# 03_mcu_oscillators.net
KiCad netlist of a schematic drawn in Altium Designer
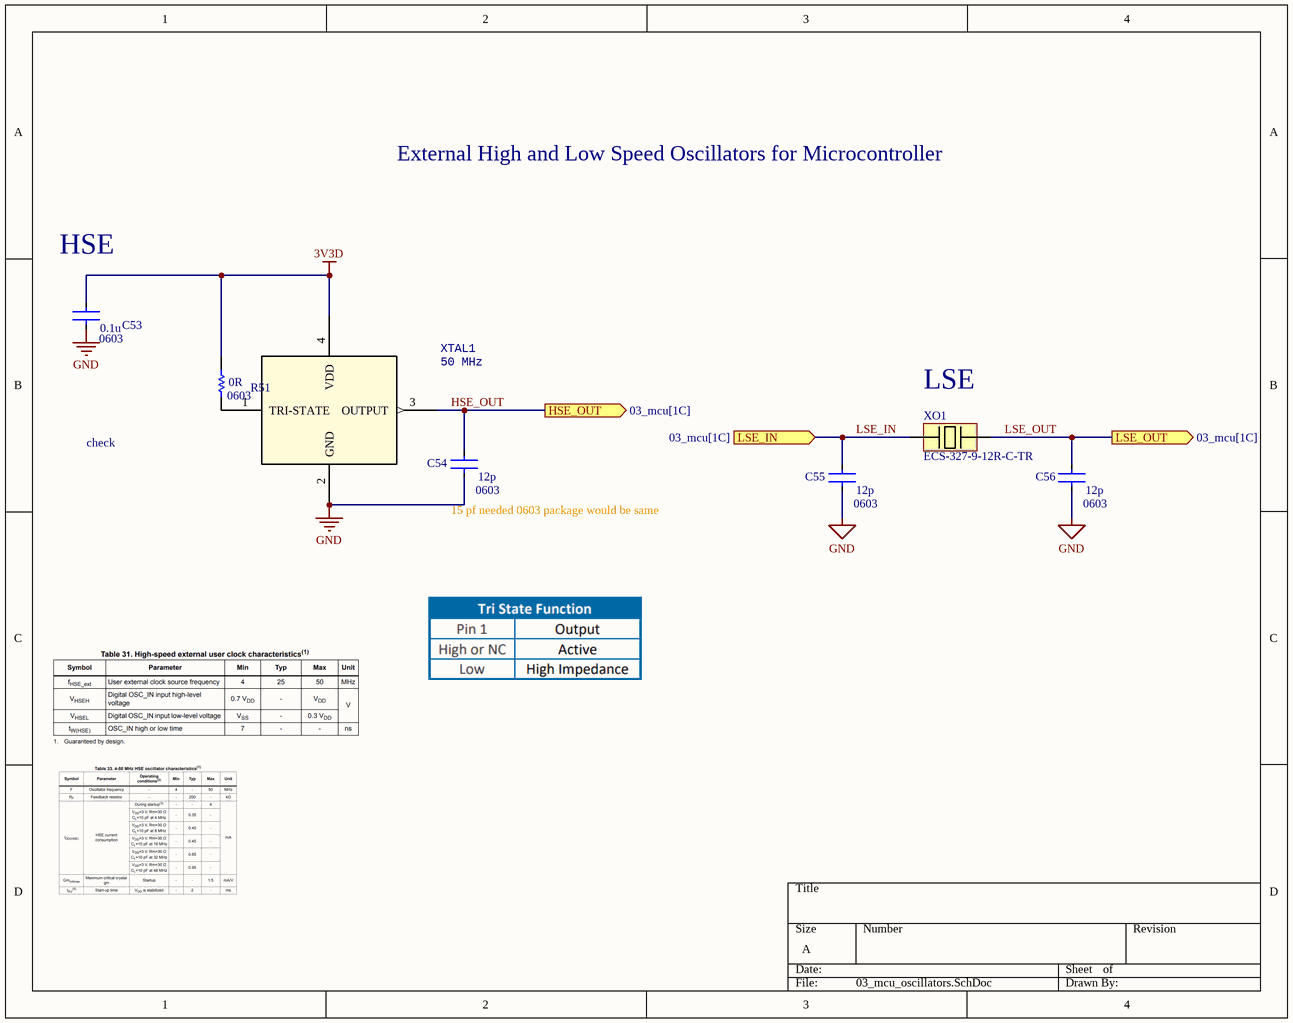
[diagram p0: 03_mcu_oscillators.SchDoc]

(export (version "E")
  (design (tool "Eeschema 10.0.6"))
  (components
    (comp (ref "C53")
      (value "CGA3E2X7R1H104K080AA")
      (footprint "CAPTDK0603")
      (description "CAP CER 0.1UF 50V X7R 0603")
      (libsource (lib "tcspc00") (part "CGA3E2X7R1H104K080AA"))
    )
    (comp (ref "C54")
      (value "CGA3E2C0G1H120J080AA")
      (footprint "CAPTDK0603")
      (description "CAP CER 12PF 50V C0G 0603")
      (libsource (lib "tcspc00") (part "CGA3E2C0G1H120J080AA"))
    )
    (comp (ref "C55")
      (value "CGA3E2C0G1H120J080AA")
      (footprint "CAPTDK0603")
      (description "CAP CER 12PF 50V C0G 0603")
      (libsource (lib "tcspc00") (part "CGA3E2C0G1H120J080AA"))
    )
    (comp (ref "C56")
      (value "CGA3E2C0G1H120J080AA")
      (footprint "CAPTDK0603")
      (description "CAP CER 12PF 50V C0G 0603")
      (libsource (lib "tcspc00") (part "CGA3E2C0G1H120J080AA"))
    )
    (comp (ref "R51")
      (value "RMCF0603ZT0R00")
      (footprint "RES-STACK-POLE-0603")
      (description "RES 0 OHM JUMPER 1/10W 0603")
      (libsource (lib "tcspc00") (part "RMCF0603ZT0R00"))
    )
    (comp (ref "XO1")
      (value "ECS-327-9-12R-C-TR")
      (footprint "LSE-32K")
      (description "Crystal 0.032768MHz ±10ppm (Tol) 9pF Flexural 70000Ohm Automotive 2-Pin Ultra Mini-CSMD T/R")
      (fields
        (field (name "MANUFACTURER") "ECS International")
        (field (name "MANUFACTURER PART NUMBER") "ECS-.327-9-12R-C-TR")
      )
      (libsource (lib "tcspc00") (part "ECS-327-9-12R-C-TR"))
    )
    (comp (ref "XTAL1")
      (value "50 MHz")
      (footprint "ECS-2520S")
      (description "XTAL OSC XO 50.0000MHZ HCMOS SMD")
      (libsource (lib "tcspc00") (part "ECS-2520S33-500-FN-TR"))
    )
  )
  (nets
    (net (code "1") (name "/HSE_OUT") (class "Default")
      (node (ref "C54") (pin "1") (pinfunction "1_1") (pintype "passive"))
      (node (ref "XTAL1") (pin "3") (pinfunction "OUTPUT_3") (pintype "output"))
    )
    (net (code "2") (name "/LSE_IN") (class "Default")
      (node (ref "C55") (pin "1") (pinfunction "1_1") (pintype "passive"))
      (node (ref "XO1") (pin "1") (pinfunction "1_1") (pintype "passive"))
    )
    (net (code "3") (name "/LSE_OUT") (class "Default")
      (node (ref "C56") (pin "1") (pinfunction "1_1") (pintype "passive"))
      (node (ref "XO1") (pin "2") (pinfunction "2_2") (pintype "passive"))
    )
    (net (code "4") (name "3V3D") (class "Default")
      (node (ref "C53") (pin "1") (pinfunction "1_1") (pintype "passive"))
      (node (ref "R51") (pin "2") (pinfunction "2_2") (pintype "passive"))
      (node (ref "XTAL1") (pin "4") (pinfunction "VDD_4") (pintype "power_in"))
    )
    (net (code "5") (name "GND") (class "Default")
      (node (ref "C53") (pin "2") (pinfunction "2_2") (pintype "passive"))
      (node (ref "C54") (pin "2") (pinfunction "2_2") (pintype "passive"))
      (node (ref "C55") (pin "2") (pinfunction "2_2") (pintype "passive"))
      (node (ref "C56") (pin "2") (pinfunction "2_2") (pintype "passive"))
      (node (ref "XTAL1") (pin "2") (pinfunction "GND_2") (pintype "power_in"))
    )
    (net (code "6") (name "Net-(XTAL1-TRI-STATE)") (class "Default")
      (node (ref "R51") (pin "1") (pinfunction "1_1") (pintype "passive"))
      (node (ref "XTAL1") (pin "1") (pinfunction "TRI-STATE_1") (pintype "passive"))
    )
  )
)
